# Alfa_b.net
KiCad netlist of a schematic drawn in EAGLE
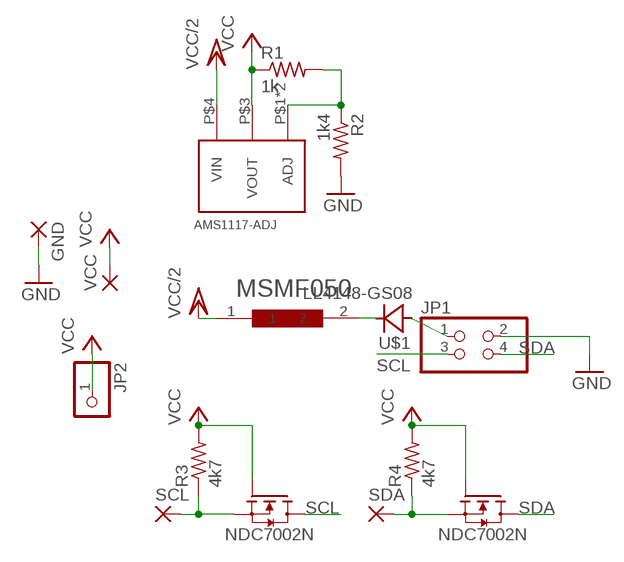
[diagram p0: schematic, sheet 1]

(export (version "E")
  (design (tool "Eeschema 10.0.6"))
  (components
    (comp (ref "AMS1117-ADJ")
      (value "AMS1117")
      (footprint "eagle-import:SOT223")
      (libsource (lib "eagle-import") (part "AMS1117"))
    )
    (comp (ref "GND")
      (value "SMD2")
      (footprint "eagle-import:SMD1,27-2,54")
      (libsource (lib "eagle-import") (part "SMD2"))
    )
    (comp (ref "JP1")
      (value "PINHD-2X2")
      (footprint "eagle-import:2X02")
      (libsource (lib "eagle-import") (part "PINHD-2X2"))
    )
    (comp (ref "JP2")
      (value "PINHD-1X1")
      (footprint "eagle-import:1X01")
      (libsource (lib "eagle-import") (part "PINHD-1X1"))
    )
    (comp (ref "MSMF050")
      (value "MF-MSMF050")
      (footprint "eagle-import:MF-MSMF050")
      (libsource (lib "eagle-import") (part "MF-MSMF050"))
    )
    (comp (ref "NDC7002N")
      (value "NDC7002N")
      (footprint "eagle-import:SOT-23-6")
      (libsource (lib "eagle-import") (part "NDC7002N"))
    )
    (comp (ref "R1")
      (value "1k")
      (footprint "eagle-import:R0603")
      (libsource (lib "eagle-import") (part "R-US_R0603"))
    )
    (comp (ref "R2")
      (value "1k4")
      (footprint "eagle-import:R0603")
      (libsource (lib "eagle-import") (part "R-US_R0603"))
    )
    (comp (ref "R3")
      (value "4k7")
      (footprint "eagle-import:R0603")
      (libsource (lib "eagle-import") (part "R-US_R0603"))
    )
    (comp (ref "R4")
      (value "4k7")
      (footprint "eagle-import:R0603")
      (libsource (lib "eagle-import") (part "R-US_R0603"))
    )
    (comp (ref "SCL")
      (value "SMD2")
      (footprint "eagle-import:SMD1,27-2,54")
      (libsource (lib "eagle-import") (part "SMD2"))
    )
    (comp (ref "SDA")
      (value "SMD2")
      (footprint "eagle-import:SMD1,27-2,54")
      (libsource (lib "eagle-import") (part "SMD2"))
    )
    (comp (ref "U$1")
      (value "LL4148-GS08")
      (footprint "eagle-import:SOD-80")
      (libsource (lib "eagle-import") (part "LL4148-GS08"))
    )
    (comp (ref "VCC")
      (value "SMD2")
      (footprint "eagle-import:SMD1,27-2,54")
      (libsource (lib "eagle-import") (part "SMD2"))
    )
  )
  (nets
    (net (code "1") (name "/SCL") (class "Default")
      (node (ref "JP1") (pin "3") (pinfunction "3_3") (pintype "passive"))
      (node (ref "NDC7002N") (pin "6") (pinfunction "D1_6") (pintype "passive"))
    )
    (net (code "2") (name "/SDA") (class "Default")
      (node (ref "JP1") (pin "4") (pinfunction "4_4") (pintype "passive"))
      (node (ref "NDC7002N") (pin "4") (pinfunction "D2_4") (pintype "passive"))
    )
    (net (code "3") (name "GND") (class "Default")
      (node (ref "GND") (pin "1") (pinfunction "P_1") (pintype "passive"))
      (node (ref "JP1") (pin "2") (pinfunction "2_2") (pintype "passive"))
      (node (ref "R2") (pin "2") (pinfunction "2_2") (pintype "passive"))
    )
    (net (code "4") (name "Net-(AMS1117-ADJ-ADJ-PadP$1)") (class "Default")
      (node (ref "AMS1117-ADJ") (pin "P$1") (pinfunction "ADJ_P$1") (pintype "bidirectional"))
      (node (ref "AMS1117-ADJ") (pin "P$2") (pinfunction "ADJ_P$2") (pintype "bidirectional"))
      (node (ref "R1") (pin "2") (pinfunction "2_2") (pintype "passive"))
      (node (ref "R2") (pin "1") (pinfunction "1_1") (pintype "passive"))
    )
    (net (code "5") (name "Net-(NDC7002N-S1)") (class "Default")
      (node (ref "NDC7002N") (pin "5") (pinfunction "S1_5") (pintype "passive"))
      (node (ref "R3") (pin "1") (pinfunction "1_1") (pintype "passive"))
      (node (ref "SCL") (pin "1") (pinfunction "P_1") (pintype "passive"))
    )
    (net (code "6") (name "Net-(NDC7002N-S2)") (class "Default")
      (node (ref "NDC7002N") (pin "2") (pinfunction "S2_2") (pintype "passive"))
      (node (ref "R4") (pin "1") (pinfunction "1_1") (pintype "passive"))
      (node (ref "SDA") (pin "1") (pinfunction "P_1") (pintype "passive"))
    )
    (net (code "7") (name "Net-(U$1-A)") (class "Default")
      (node (ref "JP1") (pin "1") (pinfunction "1_1") (pintype "passive"))
      (node (ref "U$1") (pin "1") (pinfunction "A_1") (pintype "passive"))
    )
    (net (code "8") (name "Net-(U$1-C)") (class "Default")
      (node (ref "MSMF050") (pin "2") (pinfunction "2_2") (pintype "bidirectional"))
      (node (ref "U$1") (pin "2") (pinfunction "C_2") (pintype "passive"))
    )
    (net (code "9") (name "VCC") (class "Default")
      (node (ref "AMS1117-ADJ") (pin "P$3") (pinfunction "VOUT_P$3") (pintype "bidirectional"))
      (node (ref "JP2") (pin "1") (pinfunction "1_1") (pintype "passive"))
      (node (ref "NDC7002N") (pin "1") (pinfunction "G1_1") (pintype "passive"))
      (node (ref "NDC7002N") (pin "3") (pinfunction "G2_3") (pintype "passive"))
      (node (ref "R1") (pin "1") (pinfunction "1_1") (pintype "passive"))
      (node (ref "R3") (pin "2") (pinfunction "2_2") (pintype "passive"))
      (node (ref "R4") (pin "2") (pinfunction "2_2") (pintype "passive"))
      (node (ref "VCC") (pin "1") (pinfunction "P_1") (pintype "passive"))
    )
    (net (code "10") (name "VCC{slash}2") (class "Default")
      (node (ref "AMS1117-ADJ") (pin "P$4") (pinfunction "VIN_P$4") (pintype "bidirectional"))
      (node (ref "MSMF050") (pin "1") (pinfunction "1_1") (pintype "bidirectional"))
    )
  )
)
